# 09-USBUart_PPSMUX_UARTMUX.net
KiCad netlist of a schematic drawn in Altium Designer
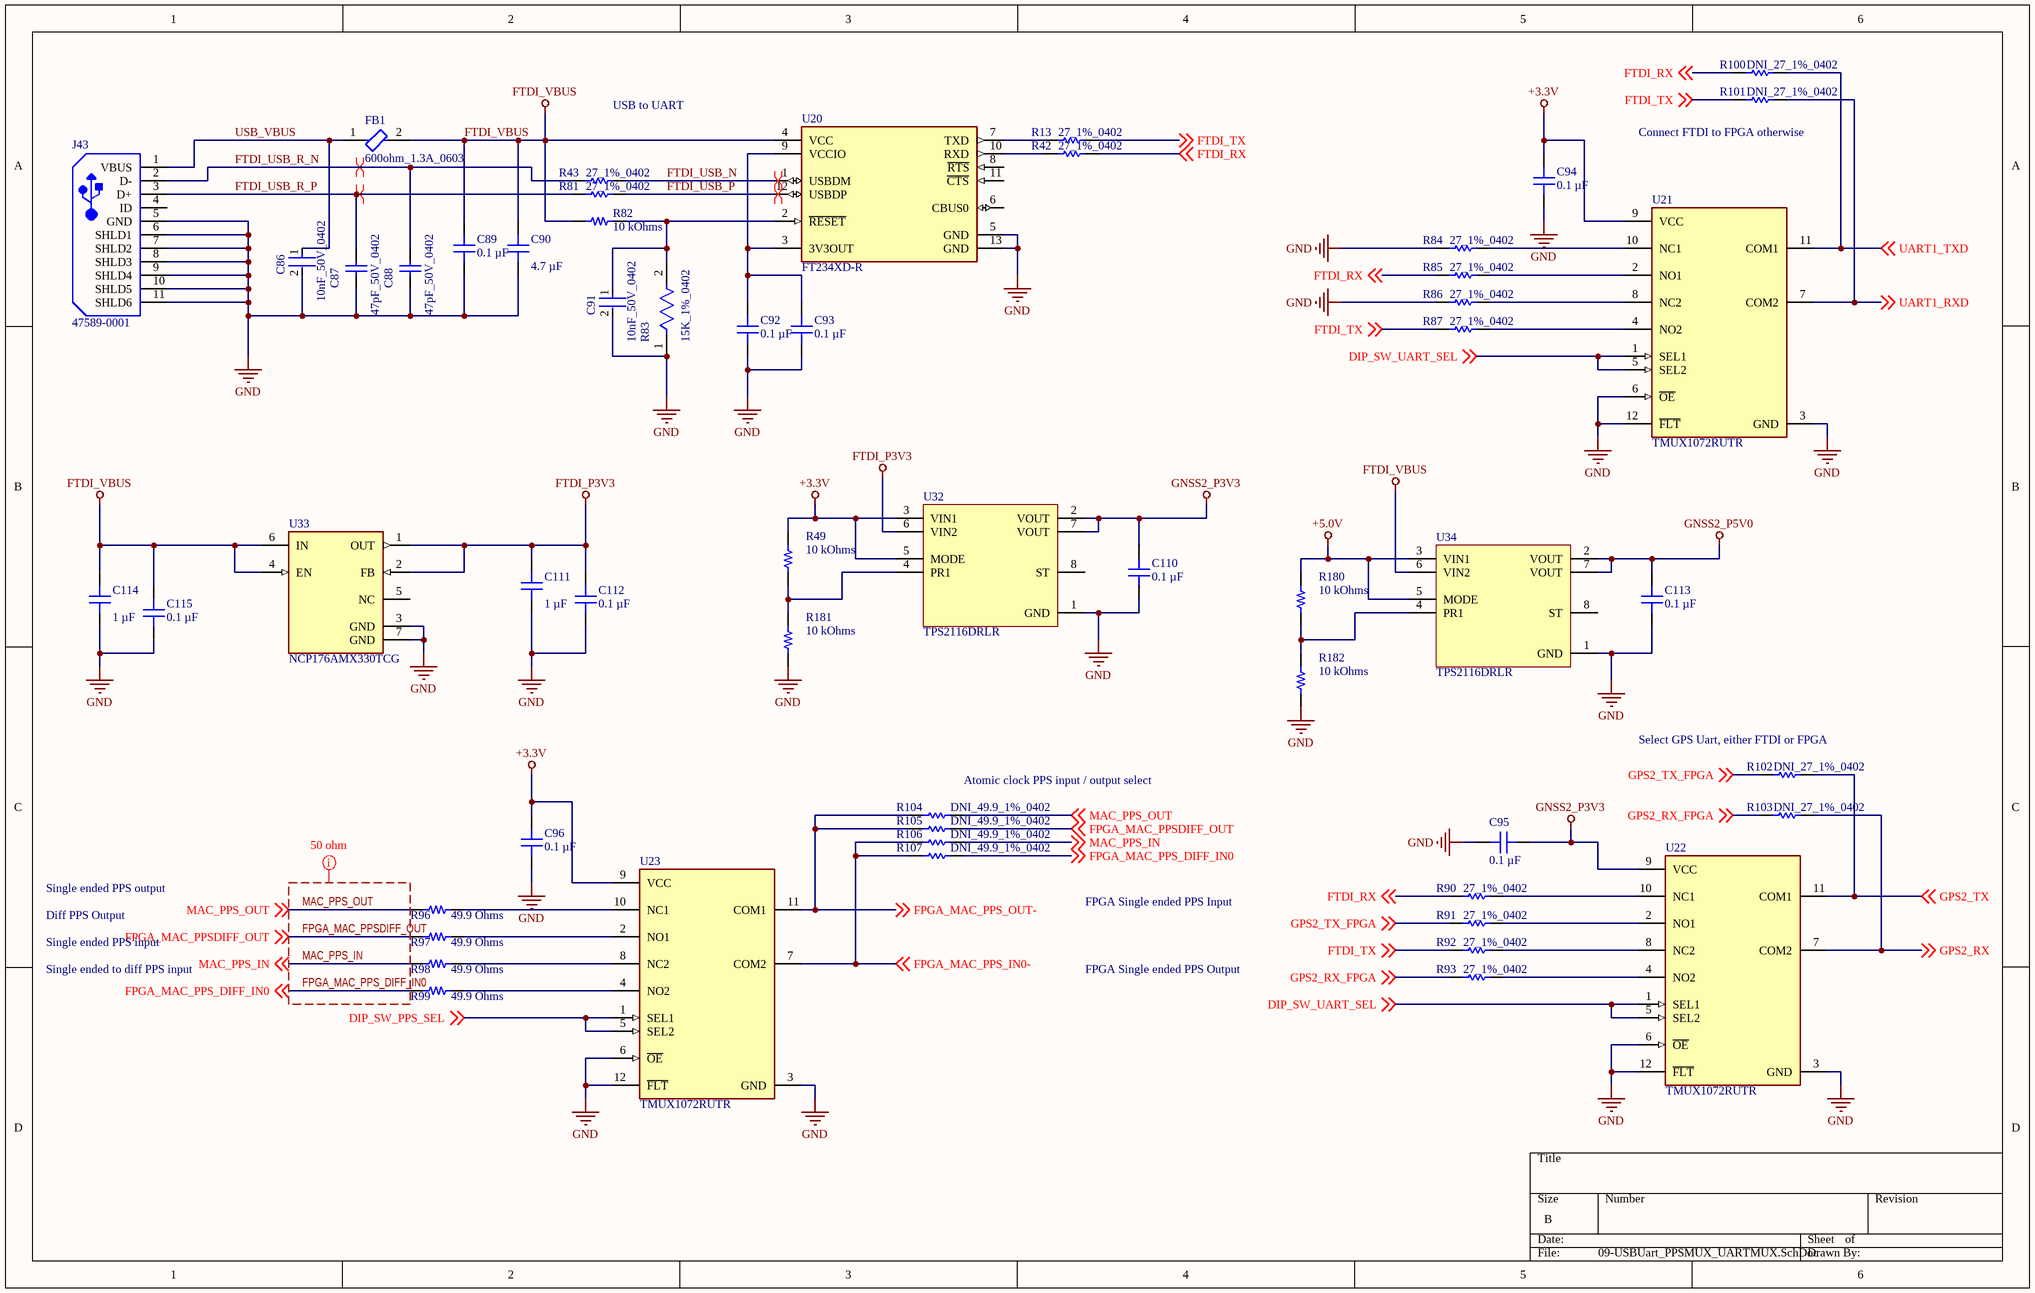
[diagram p0: 09-USBUart_PPSMUX_UARTMUX.SchDoc]

(export (version "E")
  (design (tool "Eeschema 10.0.6"))
  (components
    (comp (ref "C86")
      (value "10nF_50V_0402")
      (footprint "FP-CC0402-MFG")
      (description "CAP CER 10000PF 50V X7R 0402")
      (fields
        (field (name "OCTOPART") "https://octopart.com/cc0402krx7r9bb103-yageo-8376513")
        (field (name "MANUFACTURER PART NUMBER") "CC0402KRX7R9BB103")
      )
      (libsource (lib "Altium Content Vault") (part "11868f565c42a9108669ba33697ecf6"))
    )
    (comp (ref "C87")
      (value "47pF_50V_0402")
      (footprint "CAPC1005X55X25LL05T10")
      (fields (field (name "PART NUMBER") "GRM1555C1H470JA01D") (field (name "MANUFACTURER") "Murata"))
      (libsource (lib "Altium Content Vault") (part "CAP"))
    )
    (comp (ref "C88")
      (value "47pF_50V_0402")
      (footprint "CAPC1005X55X25LL05T10")
      (fields (field (name "PART NUMBER") "GRM1555C1H470JA01D") (field (name "MANUFACTURER") "Murata"))
      (libsource (lib "Altium Content Vault") (part "CAP"))
    )
    (comp (ref "C89")
      (value "0.1 µF")
      (footprint "CAP 0402_1005")
      (description "CAP CER 0.1UF 50V X7R 0402")
      (fields (field (name "TOLERANCE") "±10%") (field (name "PART NUMBER") "CC0402KRX7R9BB104"))
      (libsource (lib "Celestial Altium Library - altium_library") (part "Capacitor"))
    )
    (comp (ref "C90")
      (value "4.7 µF")
      (footprint "MURATA CAP GRM31C 1206_3216")
      (description "CAP CER 4.7UF 50V X7R 1206")
      (fields (field (name "TOLERANCE") "±10%") (field (name "PART NUMBER") "GRM31CR71H475KA12L"))
      (libsource (lib "Celestial Altium Library - altium_library") (part "Capacitor"))
    )
    (comp (ref "C91")
      (value "10nF_50V_0402")
      (footprint "FP-CC0402-MFG")
      (description "CAP CER 10000PF 50V X7R 0402")
      (fields
        (field (name "OCTOPART") "https://octopart.com/cc0402krx7r9bb103-yageo-8376513")
        (field (name "MANUFACTURER PART NUMBER") "CC0402KRX7R9BB103")
      )
      (libsource (lib "Altium Content Vault") (part "11868f565c42a9108669ba33697ecf6"))
    )
    (comp (ref "C92")
      (value "0.1 µF")
      (footprint "CAP 0402_1005")
      (description "CAP CER 0.1UF 50V X7R 0402")
      (fields (field (name "TOLERANCE") "±10%") (field (name "PART NUMBER") "CC0402KRX7R9BB104"))
      (libsource (lib "Celestial Altium Library - altium_library") (part "Capacitor"))
    )
    (comp (ref "C93")
      (value "0.1 µF")
      (footprint "CAP 0402_1005")
      (description "CAP CER 0.1UF 50V X7R 0402")
      (fields (field (name "TOLERANCE") "±10%") (field (name "PART NUMBER") "CC0402KRX7R9BB104"))
      (libsource (lib "Celestial Altium Library - altium_library") (part "Capacitor"))
    )
    (comp (ref "C94")
      (value "0.1 µF")
      (footprint "CAP 0402_1005")
      (description "CAP CER 0.1UF 50V X7R 0402")
      (fields (field (name "TOLERANCE") "±10%") (field (name "PART NUMBER") "CC0402KRX7R9BB104"))
      (libsource (lib "Celestial Altium Library - altium_library") (part "Capacitor"))
    )
    (comp (ref "C95")
      (value "0.1 µF")
      (footprint "CAP 0402_1005")
      (description "CAP CER 0.1UF 50V X7R 0402")
      (fields (field (name "TOLERANCE") "±10%") (field (name "PART NUMBER") "CC0402KRX7R9BB104"))
      (libsource (lib "Celestial Altium Library - altium_library") (part "Capacitor"))
    )
    (comp (ref "C96")
      (value "0.1 µF")
      (footprint "CAP 0402_1005")
      (description "CAP CER 0.1UF 50V X7R 0402")
      (fields (field (name "TOLERANCE") "±10%") (field (name "PART NUMBER") "CC0402KRX7R9BB104"))
      (libsource (lib "Celestial Altium Library - altium_library") (part "Capacitor"))
    )
    (comp (ref "C110")
      (value "0.1 µF")
      (footprint "CAP 0402_1005")
      (description "CAP CER 0.1UF 50V X7R 0402")
      (fields (field (name "TOLERANCE") "±10%") (field (name "PART NUMBER") "CC0402KRX7R9BB104"))
      (libsource (lib "Celestial Altium Library - altium_library") (part "Capacitor"))
    )
    (comp (ref "C111")
      (value "1 µF")
      (footprint "CAP 0402_1005")
      (description "CAP CER 1UF 25V X5R 0402")
      (fields (field (name "TOLERANCE") "±10%") (field (name "PART NUMBER") "CC0402KRX5R8BB105"))
      (libsource (lib "Celestial Altium Library - altium_library") (part "Capacitor"))
    )
    (comp (ref "C112")
      (value "0.1 µF")
      (footprint "CAP 0402_1005")
      (description "CAP CER 0.1UF 50V X7R 0402")
      (fields (field (name "TOLERANCE") "±10%") (field (name "PART NUMBER") "CC0402KRX7R9BB104"))
      (libsource (lib "Celestial Altium Library - altium_library") (part "Capacitor"))
    )
    (comp (ref "C113")
      (value "0.1 µF")
      (footprint "CAP 0402_1005")
      (description "CAP CER 0.1UF 50V X7R 0402")
      (fields (field (name "TOLERANCE") "±10%") (field (name "PART NUMBER") "CC0402KRX7R9BB104"))
      (libsource (lib "Celestial Altium Library - altium_library") (part "Capacitor"))
    )
    (comp (ref "C114")
      (value "1 µF")
      (footprint "CAP 0402_1005")
      (description "CAP CER 1UF 25V X5R 0402")
      (fields (field (name "TOLERANCE") "±10%") (field (name "PART NUMBER") "CC0402KRX5R8BB105"))
      (libsource (lib "Celestial Altium Library - altium_library") (part "Capacitor"))
    )
    (comp (ref "C115")
      (value "0.1 µF")
      (footprint "CAP 0402_1005")
      (description "CAP CER 0.1UF 50V X7R 0402")
      (fields (field (name "TOLERANCE") "±10%") (field (name "PART NUMBER") "CC0402KRX7R9BB104"))
      (libsource (lib "Celestial Altium Library - altium_library") (part "Capacitor"))
    )
    (comp (ref "FB1")
      (value "600ohm_1.3A_0603")
      (footprint "FP-BLM18-0_15-t0_8-IPC_A")
      (description "Chip Ferrite Bead, 0603, 600Ω @ 100MHz, 0.15Ω, 25%, 1.3A")
      (fields (field (name "TOLERANCE") "25%"))
      (libsource (lib "Altium Content Vault") (part "5f30dd21d616792df468990f7003faa"))
    )
    (comp (ref "J43")
      (value "47589-0001")
      (footprint "MOLX-47589-0001_V")
      (description "Right Angle Female Type AB Micro USB Connector, 30 V, 1.8 A, -30 to 85 degC, RoHS, Tape and Reel")
      (fields (field (name "MANUFACTURER") "Molex"))
      (libsource (lib "Altium Content Vault") (part "USB-5-6SHLD"))
    )
    (comp (ref "R13")
      (value "27_1%_0402")
      (footprint "RESC1005X40X25NL05T05")
      (fields (field (name "PART NUMBER") "CRCW040227R0FKED") (field (name "MANUFACTURER") "Vishay Dale"))
      (libsource (lib "Altium Content Vault") (part "RES"))
    )
    (comp (ref "R42")
      (value "27_1%_0402")
      (footprint "RESC1005X40X25NL05T05")
      (fields (field (name "PART NUMBER") "CRCW040227R0FKED") (field (name "MANUFACTURER") "Vishay Dale"))
      (libsource (lib "Altium Content Vault") (part "RES"))
    )
    (comp (ref "R43")
      (value "27_1%_0402")
      (footprint "RESC1005X40X25NL05T05")
      (fields (field (name "PART NUMBER") "CRCW040227R0FKED") (field (name "MANUFACTURER") "Vishay Dale"))
      (libsource (lib "Altium Content Vault") (part "RES"))
    )
    (comp (ref "R49")
      (value "10 kOhms")
      (footprint "YAGEO RES 0402_1005")
      (description "RES 10K OHM 1% 1/16W 0402")
      (fields (field (name "PART NUMBER") "RC0402FR-0710KL") (field (name "MANUFACTURER") "Yageo"))
      (libsource (lib "Celestial Altium Library - altium_library") (part "Resistor"))
    )
    (comp (ref "R81")
      (value "27_1%_0402")
      (footprint "RESC1005X40X25NL05T05")
      (fields (field (name "PART NUMBER") "CRCW040227R0FKED") (field (name "MANUFACTURER") "Vishay Dale"))
      (libsource (lib "Altium Content Vault") (part "RES"))
    )
    (comp (ref "R82")
      (value "10 kOhms")
      (footprint "YAGEO RES 0402_1005")
      (description "RES 10K OHM 1% 1/16W 0402")
      (fields (field (name "PART NUMBER") "RC0402FR-0710KL") (field (name "MANUFACTURER") "Yageo"))
      (libsource (lib "Celestial Altium Library - altium_library") (part "Resistor"))
    )
    (comp (ref "R83")
      (value "15K_1%_0402")
      (footprint "FP-ERJ2R-MFG")
      (description "RES SMD 15K OHM 1% 1/10W 0402")
      (fields (field (name "TOLERANCE") "1%") (field (name "MANUFACTURER PART NUMBER") "ERJ-2RKF1502X"))
      (libsource (lib "Altium Content Vault") (part "1029c3af85768c4190bb7ad29bc67b5"))
    )
    (comp (ref "R84")
      (value "27_1%_0402")
      (footprint "RESC1005X40X25NL05T05")
      (fields (field (name "PART NUMBER") "CRCW040227R0FKED") (field (name "MANUFACTURER") "Vishay Dale"))
      (libsource (lib "Altium Content Vault") (part "RES"))
    )
    (comp (ref "R85")
      (value "27_1%_0402")
      (footprint "RESC1005X40X25NL05T05")
      (fields (field (name "PART NUMBER") "CRCW040227R0FKED") (field (name "MANUFACTURER") "Vishay Dale"))
      (libsource (lib "Altium Content Vault") (part "RES"))
    )
    (comp (ref "R86")
      (value "27_1%_0402")
      (footprint "RESC1005X40X25NL05T05")
      (fields (field (name "PART NUMBER") "CRCW040227R0FKED") (field (name "MANUFACTURER") "Vishay Dale"))
      (libsource (lib "Altium Content Vault") (part "RES"))
    )
    (comp (ref "R87")
      (value "27_1%_0402")
      (footprint "RESC1005X40X25NL05T05")
      (fields (field (name "PART NUMBER") "CRCW040227R0FKED") (field (name "MANUFACTURER") "Vishay Dale"))
      (libsource (lib "Altium Content Vault") (part "RES"))
    )
    (comp (ref "R90")
      (value "27_1%_0402")
      (footprint "RESC1005X40X25NL05T05")
      (fields (field (name "PART NUMBER") "CRCW040227R0FKED") (field (name "MANUFACTURER") "Vishay Dale"))
      (libsource (lib "Altium Content Vault") (part "RES"))
    )
    (comp (ref "R91")
      (value "27_1%_0402")
      (footprint "RESC1005X40X25NL05T05")
      (fields (field (name "PART NUMBER") "CRCW040227R0FKED") (field (name "MANUFACTURER") "Vishay Dale"))
      (libsource (lib "Altium Content Vault") (part "RES"))
    )
    (comp (ref "R92")
      (value "27_1%_0402")
      (footprint "RESC1005X40X25NL05T05")
      (fields (field (name "PART NUMBER") "CRCW040227R0FKED") (field (name "MANUFACTURER") "Vishay Dale"))
      (libsource (lib "Altium Content Vault") (part "RES"))
    )
    (comp (ref "R93")
      (value "27_1%_0402")
      (footprint "RESC1005X40X25NL05T05")
      (fields (field (name "PART NUMBER") "CRCW040227R0FKED") (field (name "MANUFACTURER") "Vishay Dale"))
      (libsource (lib "Altium Content Vault") (part "RES"))
    )
    (comp (ref "R96")
      (value "49.9 Ohms")
      (footprint "YAGEO RES 0402_1005")
      (description "RES 49.9 OHM 1% 1/16W 0402")
      (fields (field (name "MANUFACTURER") "Yageo") (field (name "PART NUMBER") "RC0402FR-0749R9L"))
      (libsource (lib "Celestial Altium Library - altium_library") (part "Resistor"))
    )
    (comp (ref "R97")
      (value "49.9 Ohms")
      (footprint "YAGEO RES 0402_1005")
      (description "RES 49.9 OHM 1% 1/16W 0402")
      (fields (field (name "MANUFACTURER") "Yageo") (field (name "PART NUMBER") "RC0402FR-0749R9L"))
      (libsource (lib "Celestial Altium Library - altium_library") (part "Resistor"))
    )
    (comp (ref "R98")
      (value "49.9 Ohms")
      (footprint "YAGEO RES 0402_1005")
      (description "RES 49.9 OHM 1% 1/16W 0402")
      (fields (field (name "MANUFACTURER") "Yageo") (field (name "PART NUMBER") "RC0402FR-0749R9L"))
      (libsource (lib "Celestial Altium Library - altium_library") (part "Resistor"))
    )
    (comp (ref "R99")
      (value "49.9 Ohms")
      (footprint "YAGEO RES 0402_1005")
      (description "RES 49.9 OHM 1% 1/16W 0402")
      (fields (field (name "MANUFACTURER") "Yageo") (field (name "PART NUMBER") "RC0402FR-0749R9L"))
      (libsource (lib "Celestial Altium Library - altium_library") (part "Resistor"))
    )
    (comp (ref "R100")
      (value "DNI_27_1%_0402")
      (footprint "RESC1005X40X25NL05T05")
      (fields (field (name "PART NUMBER") "CRCW040227R0FKED") (field (name "MANUFACTURER") "Vishay Dale"))
      (libsource (lib "Altium Content Vault") (part "RES"))
    )
    (comp (ref "R101")
      (value "DNI_27_1%_0402")
      (footprint "RESC1005X40X25NL05T05")
      (fields (field (name "PART NUMBER") "CRCW040227R0FKED") (field (name "MANUFACTURER") "Vishay Dale"))
      (libsource (lib "Altium Content Vault") (part "RES"))
    )
    (comp (ref "R102")
      (value "DNI_27_1%_0402")
      (footprint "RESC1005X40X25NL05T05")
      (fields (field (name "PART NUMBER") "CRCW040227R0FKED") (field (name "MANUFACTURER") "Vishay Dale"))
      (libsource (lib "Altium Content Vault") (part "RES"))
    )
    (comp (ref "R103")
      (value "DNI_27_1%_0402")
      (footprint "RESC1005X40X25NL05T05")
      (fields (field (name "PART NUMBER") "CRCW040227R0FKED") (field (name "MANUFACTURER") "Vishay Dale"))
      (libsource (lib "Altium Content Vault") (part "RES"))
    )
    (comp (ref "R104")
      (value "DNI_49.9_1%_0402")
      (footprint "RESC1005X40X25LL05T10")
      (fields (field (name "MANUFACTURER") "Yageo / Phycomp") (field (name "PART NUMBER") "RC0402FR-0749R9L"))
      (libsource (lib "Altium Content Vault") (part "RES"))
    )
    (comp (ref "R105")
      (value "DNI_49.9_1%_0402")
      (footprint "RESC1005X40X25LL05T10")
      (fields (field (name "MANUFACTURER") "Yageo / Phycomp") (field (name "PART NUMBER") "RC0402FR-0749R9L"))
      (libsource (lib "Altium Content Vault") (part "RES"))
    )
    (comp (ref "R106")
      (value "DNI_49.9_1%_0402")
      (footprint "RESC1005X40X25LL05T10")
      (fields (field (name "MANUFACTURER") "Yageo / Phycomp") (field (name "PART NUMBER") "RC0402FR-0749R9L"))
      (libsource (lib "Altium Content Vault") (part "RES"))
    )
    (comp (ref "R107")
      (value "DNI_49.9_1%_0402")
      (footprint "RESC1005X40X25LL05T10")
      (fields (field (name "MANUFACTURER") "Yageo / Phycomp") (field (name "PART NUMBER") "RC0402FR-0749R9L"))
      (libsource (lib "Altium Content Vault") (part "RES"))
    )
    (comp (ref "R180")
      (value "10 kOhms")
      (footprint "YAGEO RES 0402_1005")
      (description "RES 10K OHM 1% 1/16W 0402")
      (fields (field (name "PART NUMBER") "RC0402FR-0710KL") (field (name "MANUFACTURER") "Yageo"))
      (libsource (lib "Celestial Altium Library - altium_library") (part "Resistor"))
    )
    (comp (ref "R181")
      (value "10 kOhms")
      (footprint "YAGEO RES 0402_1005")
      (description "RES 10K OHM 1% 1/16W 0402")
      (fields (field (name "PART NUMBER") "RC0402FR-0710KL") (field (name "MANUFACTURER") "Yageo"))
      (libsource (lib "Celestial Altium Library - altium_library") (part "Resistor"))
    )
    (comp (ref "R182")
      (value "10 kOhms")
      (footprint "YAGEO RES 0402_1005")
      (description "RES 10K OHM 1% 1/16W 0402")
      (fields (field (name "PART NUMBER") "RC0402FR-0710KL") (field (name "MANUFACTURER") "Yageo"))
      (libsource (lib "Celestial Altium Library - altium_library") (part "Resistor"))
    )
    (comp (ref "U20")
      (value "FT234XD-R")
      (footprint "FP-DFN-12-IPC_B")
      (description "IC USB SERIAL BASIC UART 12DFN")
      (libsource (lib "Altium Content Vault") (part "4bef3367ed9f9051bcb84ab46edda1c"))
    )
    (comp (ref "U21")
      (value "TMUX1072RUTR")
      (footprint "FP-RUT0012A-MFG")
      (description "IC SWITCH SPDT DUAL 12UQFN")
      (libsource (lib "Altium Content Vault") (part "12a319ab100cd6cfe745e35972674f5"))
    )
    (comp (ref "U22")
      (value "TMUX1072RUTR")
      (footprint "FP-RUT0012A-MFG")
      (description "IC SWITCH SPDT DUAL 12UQFN")
      (libsource (lib "Altium Content Vault") (part "12a319ab100cd6cfe745e35972674f5"))
    )
    (comp (ref "U23")
      (value "TMUX1072RUTR")
      (footprint "FP-RUT0012A-MFG")
      (description "IC SWITCH SPDT DUAL 12UQFN")
      (libsource (lib "Altium Content Vault") (part "12a319ab100cd6cfe745e35972674f5"))
    )
    (comp (ref "U32")
      (value "TPS2116DRLR")
      (footprint "IC_TPS2116")
      (description "1.6-V to 5.5-V, 40-mΩ, 2.5-A, low-IQ, priority power multiplexer 8-SOT-5X3 -40 to 125")
      (fields (field (name "MF") "Texas Instruments"))
      (libsource (lib "LotusSound") (part "IC_TPS2116DRLR"))
    )
    (comp (ref "U33")
      (value "NCP176AMX330TCG")
      (footprint "FP-711AT-MFG")
      (description "IC REG LINEAR 3.3V 500MA 6XDFN")
      (fields
        (field (name "MANUFACTURER") "ON Semiconductor")
        (field (name "OCTOPART") "https://octopart.com/ncp176amx330tcg-on+semiconductor-61522616")
      )
      (libsource (lib "Altium Content Vault") (part "a38d0f79c2a9f01c07a7e52882ed186"))
    )
    (comp (ref "U34")
      (value "TPS2116DRLR")
      (footprint "IC_TPS2116")
      (description "1.6-V to 5.5-V, 40-mΩ, 2.5-A, low-IQ, priority power multiplexer 8-SOT-5X3 -40 to 125")
      (fields (field (name "MF") "Texas Instruments"))
      (libsource (lib "LotusSound") (part "IC_TPS2116DRLR"))
    )
  )
  (nets
    (net (code "1") (name "+3.3V") (class "Default")
      (node (ref "C94") (pin "1") (pinfunction "1_1") (pintype "passive"))
      (node (ref "C96") (pin "1") (pinfunction "1_1") (pintype "passive"))
      (node (ref "R49") (pin "2") (pinfunction "2_2") (pintype "passive"))
      (node (ref "U21") (pin "9") (pinfunction "VCC_9") (pintype "power_in"))
      (node (ref "U23") (pin "9") (pinfunction "VCC_9") (pintype "power_in"))
      (node (ref "U32") (pin "3") (pinfunction "VIN1_3") (pintype "passive"))
      (node (ref "U32") (pin "5") (pinfunction "MODE_5") (pintype "passive"))
    )
    (net (code "2") (name "+5.0V") (class "Default")
      (node (ref "R180") (pin "2") (pinfunction "2_2") (pintype "passive"))
      (node (ref "U34") (pin "3") (pinfunction "VIN1_3") (pintype "passive"))
      (node (ref "U34") (pin "5") (pinfunction "MODE_5") (pintype "passive"))
    )
    (net (code "3") (name "/FTDI_USB_N") (class "Default")
      (node (ref "R43") (pin "2") (pinfunction "2_2") (pintype "passive"))
      (node (ref "U20") (pin "1") (pinfunction "USBDM_1") (pintype "bidirectional"))
    )
    (net (code "4") (name "/FTDI_USB_P") (class "Default")
      (node (ref "R81") (pin "2") (pinfunction "2_2") (pintype "passive"))
      (node (ref "U20") (pin "12") (pinfunction "USBDP_12") (pintype "bidirectional"))
    )
    (net (code "5") (name "/FTDI_USB_R_N") (class "Default")
      (node (ref "C88") (pin "2") (pinfunction "2_2") (pintype "passive"))
      (node (ref "J43") (pin "2") (pinfunction "D-_2") (pintype "passive"))
      (node (ref "R43") (pin "1") (pinfunction "1_1") (pintype "passive"))
    )
    (net (code "6") (name "/FTDI_USB_R_P") (class "Default")
      (node (ref "C87") (pin "2") (pinfunction "2_2") (pintype "passive"))
      (node (ref "J43") (pin "3") (pinfunction "D+_3") (pintype "passive"))
      (node (ref "R81") (pin "1") (pinfunction "1_1") (pintype "passive"))
    )
    (net (code "7") (name "/USB_VBUS") (class "Default")
      (node (ref "C86") (pin "1") (pinfunction "1_1") (pintype "passive"))
      (node (ref "FB1") (pin "1") (pinfunction "1_1") (pintype "passive"))
      (node (ref "J43") (pin "1") (pinfunction "VBUS_1") (pintype "passive"))
    )
    (net (code "8") (name "DIP_SW_PPS_SEL") (class "Default")
      (node (ref "U23") (pin "1") (pinfunction "SEL1_1") (pintype "input"))
      (node (ref "U23") (pin "5") (pinfunction "SEL2_5") (pintype "input"))
    )
    (net (code "9") (name "DIP_SW_UART_SEL") (class "Default")
      (node (ref "U21") (pin "1") (pinfunction "SEL1_1") (pintype "input"))
      (node (ref "U21") (pin "5") (pinfunction "SEL2_5") (pintype "input"))
      (node (ref "U22") (pin "1") (pinfunction "SEL1_1") (pintype "input"))
      (node (ref "U22") (pin "5") (pinfunction "SEL2_5") (pintype "input"))
    )
    (net (code "10") (name "FPGA_MAC_PPSDIFF_OUT") (class "Default")
      (node (ref "R105") (pin "2") (pinfunction "2_2") (pintype "passive"))
      (node (ref "R97") (pin "1") (pinfunction "1_1") (pintype "passive"))
    )
    (net (code "11") (name "FPGA_MAC_PPS_DIFF_IN0") (class "Default")
      (node (ref "R107") (pin "2") (pinfunction "2_2") (pintype "passive"))
      (node (ref "R99") (pin "1") (pinfunction "1_1") (pintype "passive"))
    )
    (net (code "12") (name "FPGA_MAC_PPS_IN0-") (class "Default")
      (node (ref "R106") (pin "1") (pinfunction "1_1") (pintype "passive"))
      (node (ref "R107") (pin "1") (pinfunction "1_1") (pintype "passive"))
      (node (ref "U23") (pin "7") (pinfunction "COM2_7") (pintype "passive"))
    )
    (net (code "13") (name "FPGA_MAC_PPS_OUT-") (class "Default")
      (node (ref "R104") (pin "1") (pinfunction "1_1") (pintype "passive"))
      (node (ref "R105") (pin "1") (pinfunction "1_1") (pintype "passive"))
      (node (ref "U23") (pin "11") (pinfunction "COM1_11") (pintype "passive"))
    )
    (net (code "14") (name "FTDI_P3V3") (class "Default")
      (node (ref "C111") (pin "2") (pinfunction "2_2") (pintype "passive"))
      (node (ref "C112") (pin "1") (pinfunction "1_1") (pintype "passive"))
      (node (ref "U32") (pin "6") (pinfunction "VIN2_6") (pintype "passive"))
      (node (ref "U33") (pin "1") (pinfunction "OUT_1") (pintype "output"))
      (node (ref "U33") (pin "2") (pinfunction "FB_2") (pintype "input"))
    )
    (net (code "15") (name "FTDI_RX") (class "Default")
      (node (ref "R100") (pin "1") (pinfunction "1_1") (pintype "passive"))
      (node (ref "R42") (pin "2") (pinfunction "2_2") (pintype "passive"))
      (node (ref "R85") (pin "1") (pinfunction "1_1") (pintype "passive"))
      (node (ref "R90") (pin "1") (pinfunction "1_1") (pintype "passive"))
    )
    (net (code "16") (name "FTDI_TX") (class "Default")
      (node (ref "R101") (pin "1") (pinfunction "1_1") (pintype "passive"))
      (node (ref "R13") (pin "2") (pinfunction "2_2") (pintype "passive"))
      (node (ref "R87") (pin "1") (pinfunction "1_1") (pintype "passive"))
      (node (ref "R92") (pin "1") (pinfunction "1_1") (pintype "passive"))
    )
    (net (code "17") (name "FTDI_VBUS") (class "Default")
      (node (ref "C114") (pin "2") (pinfunction "2_2") (pintype "passive"))
      (node (ref "C115") (pin "1") (pinfunction "1_1") (pintype "passive"))
      (node (ref "C89") (pin "1") (pinfunction "1_1") (pintype "passive"))
      (node (ref "C90") (pin "2") (pinfunction "2_2") (pintype "passive"))
      (node (ref "FB1") (pin "2") (pinfunction "2_2") (pintype "passive"))
      (node (ref "R82") (pin "2") (pinfunction "2_2") (pintype "passive"))
      (node (ref "U20") (pin "4") (pinfunction "VCC_4") (pintype "power_in"))
      (node (ref "U33") (pin "4") (pinfunction "EN_4") (pintype "input"))
      (node (ref "U33") (pin "6") (pinfunction "IN_6") (pintype "power_in"))
      (node (ref "U34") (pin "6") (pinfunction "VIN2_6") (pintype "passive"))
    )
    (net (code "18") (name "GND") (class "Default")
      (node (ref "C110") (pin "2") (pinfunction "2_2") (pintype "passive"))
      (node (ref "C111") (pin "1") (pinfunction "1_1") (pintype "passive"))
      (node (ref "C112") (pin "2") (pinfunction "2_2") (pintype "passive"))
      (node (ref "C113") (pin "2") (pinfunction "2_2") (pintype "passive"))
      (node (ref "C114") (pin "1") (pinfunction "1_1") (pintype "passive"))
      (node (ref "C115") (pin "2") (pinfunction "2_2") (pintype "passive"))
      (node (ref "C86") (pin "2") (pinfunction "2_2") (pintype "passive"))
      (node (ref "C87") (pin "1") (pinfunction "1_1") (pintype "passive"))
      (node (ref "C88") (pin "1") (pinfunction "1_1") (pintype "passive"))
      (node (ref "C89") (pin "2") (pinfunction "2_2") (pintype "passive"))
      (node (ref "C90") (pin "1") (pinfunction "1_1") (pintype "passive"))
      (node (ref "C91") (pin "2") (pinfunction "2_2") (pintype "passive"))
      (node (ref "C92") (pin "2") (pinfunction "2_2") (pintype "passive"))
      (node (ref "C93") (pin "2") (pinfunction "2_2") (pintype "passive"))
      (node (ref "C94") (pin "2") (pinfunction "2_2") (pintype "passive"))
      (node (ref "C95") (pin "2") (pinfunction "2_2") (pintype "passive"))
      (node (ref "C96") (pin "2") (pinfunction "2_2") (pintype "passive"))
      (node (ref "J43") (pin "10") (pinfunction "SHLD5_10") (pintype "passive"))
      (node (ref "J43") (pin "11") (pinfunction "SHLD6_11") (pintype "passive"))
      (node (ref "J43") (pin "5") (pinfunction "GND_5") (pintype "passive"))
      (node (ref "J43") (pin "6") (pinfunction "SHLD1_6") (pintype "passive"))
      (node (ref "J43") (pin "7") (pinfunction "SHLD2_7") (pintype "passive"))
      (node (ref "J43") (pin "8") (pinfunction "SHLD3_8") (pintype "passive"))
      (node (ref "J43") (pin "9") (pinfunction "SHLD4_9") (pintype "passive"))
      (node (ref "R181") (pin "1") (pinfunction "1_1") (pintype "passive"))
      (node (ref "R182") (pin "1") (pinfunction "1_1") (pintype "passive"))
      (node (ref "R83") (pin "1") (pinfunction "1_1") (pintype "passive"))
      (node (ref "R84") (pin "1") (pinfunction "1_1") (pintype "passive"))
      (node (ref "R86") (pin "1") (pinfunction "1_1") (pintype "passive"))
      (node (ref "U20") (pin "13") (pinfunction "GND_13") (pintype "power_in"))
      (node (ref "U20") (pin "5") (pinfunction "GND_5") (pintype "power_in"))
      (node (ref "U21") (pin "12") (pinfunction "~{FLT}_12") (pintype "open_collector"))
      (node (ref "U21") (pin "3") (pinfunction "GND_3") (pintype "power_in"))
      (node (ref "U21") (pin "6") (pinfunction "~{OE}_6") (pintype "input"))
      (node (ref "U22") (pin "12") (pinfunction "~{FLT}_12") (pintype "open_collector"))
      (node (ref "U22") (pin "3") (pinfunction "GND_3") (pintype "power_in"))
      (node (ref "U22") (pin "6") (pinfunction "~{OE}_6") (pintype "input"))
      (node (ref "U23") (pin "12") (pinfunction "~{FLT}_12") (pintype "open_collector"))
      (node (ref "U23") (pin "3") (pinfunction "GND_3") (pintype "power_in"))
      (node (ref "U23") (pin "6") (pinfunction "~{OE}_6") (pintype "input"))
      (node (ref "U32") (pin "1") (pinfunction "GND_1") (pintype "passive"))
      (node (ref "U33") (pin "3") (pinfunction "GND_3") (pintype "power_in"))
      (node (ref "U33") (pin "7") (pinfunction "GND_7") (pintype "power_in"))
      (node (ref "U34") (pin "1") (pinfunction "GND_1") (pintype "passive"))
    )
    (net (code "19") (name "GNSS2_P3V3") (class "Default")
      (node (ref "C110") (pin "1") (pinfunction "1_1") (pintype "passive"))
      (node (ref "C95") (pin "1") (pinfunction "1_1") (pintype "passive"))
      (node (ref "U22") (pin "9") (pinfunction "VCC_9") (pintype "power_in"))
      (node (ref "U32") (pin "2") (pinfunction "VOUT_2") (pintype "passive"))
      (node (ref "U32") (pin "7") (pinfunction "VOUT_7") (pintype "passive"))
    )
    (net (code "20") (name "GNSS2_P5V0") (class "Default")
      (node (ref "C113") (pin "1") (pinfunction "1_1") (pintype "passive"))
      (node (ref "U34") (pin "2") (pinfunction "VOUT_2") (pintype "passive"))
      (node (ref "U34") (pin "7") (pinfunction "VOUT_7") (pintype "passive"))
    )
    (net (code "21") (name "GPS2_RX") (class "Default")
      (node (ref "R103") (pin "2") (pinfunction "2_2") (pintype "passive"))
      (node (ref "U22") (pin "7") (pinfunction "COM2_7") (pintype "passive"))
    )
    (net (code "22") (name "GPS2_RX_FPGA") (class "Default")
      (node (ref "R103") (pin "1") (pinfunction "1_1") (pintype "passive"))
      (node (ref "R93") (pin "1") (pinfunction "1_1") (pintype "passive"))
    )
    (net (code "23") (name "GPS2_TX") (class "Default")
      (node (ref "R102") (pin "2") (pinfunction "2_2") (pintype "passive"))
      (node (ref "U22") (pin "11") (pinfunction "COM1_11") (pintype "passive"))
    )
    (net (code "24") (name "GPS2_TX_FPGA") (class "Default")
      (node (ref "R102") (pin "1") (pinfunction "1_1") (pintype "passive"))
      (node (ref "R91") (pin "1") (pinfunction "1_1") (pintype "passive"))
    )
    (net (code "25") (name "MAC_PPS_IN") (class "Default")
      (node (ref "R106") (pin "2") (pinfunction "2_2") (pintype "passive"))
      (node (ref "R98") (pin "1") (pinfunction "1_1") (pintype "passive"))
    )
    (net (code "26") (name "MAC_PPS_OUT") (class "Default")
      (node (ref "R104") (pin "2") (pinfunction "2_2") (pintype "passive"))
      (node (ref "R96") (pin "1") (pinfunction "1_1") (pintype "passive"))
    )
    (net (code "27") (name "Net-(U20-3V3OUT)") (class "Default")
      (node (ref "C92") (pin "1") (pinfunction "1_1") (pintype "passive"))
      (node (ref "C93") (pin "1") (pinfunction "1_1") (pintype "passive"))
      (node (ref "U20") (pin "3") (pinfunction "3V3OUT_3") (pintype "power_in"))
      (node (ref "U20") (pin "9") (pinfunction "VCCIO_9") (pintype "power_in"))
    )
    (net (code "28") (name "Net-(U20-RXD)") (class "Default")
      (node (ref "R42") (pin "1") (pinfunction "1_1") (pintype "passive"))
      (node (ref "U20") (pin "10") (pinfunction "RXD_10") (pintype "output"))
    )
    (net (code "29") (name "Net-(U20-TXD)") (class "Default")
      (node (ref "R13") (pin "1") (pinfunction "1_1") (pintype "passive"))
      (node (ref "U20") (pin "7") (pinfunction "TXD_7") (pintype "output"))
    )
    (net (code "30") (name "Net-(U20-~{RESET})") (class "Default")
      (node (ref "C91") (pin "1") (pinfunction "1_1") (pintype "passive"))
      (node (ref "R82") (pin "1") (pinfunction "1_1") (pintype "passive"))
      (node (ref "R83") (pin "2") (pinfunction "2_2") (pintype "passive"))
      (node (ref "U20") (pin "2") (pinfunction "~{RESET}_2") (pintype "input"))
    )
    (net (code "31") (name "Net-(U21-NC1)") (class "Default")
      (node (ref "R84") (pin "2") (pinfunction "2_2") (pintype "passive"))
      (node (ref "U21") (pin "10") (pinfunction "NC1_10") (pintype "passive"))
    )
    (net (code "32") (name "Net-(U21-NC2)") (class "Default")
      (node (ref "R86") (pin "2") (pinfunction "2_2") (pintype "passive"))
      (node (ref "U21") (pin "8") (pinfunction "NC2_8") (pintype "passive"))
    )
    (net (code "33") (name "Net-(U21-NO1)") (class "Default")
      (node (ref "R85") (pin "2") (pinfunction "2_2") (pintype "passive"))
      (node (ref "U21") (pin "2") (pinfunction "NO1_2") (pintype "passive"))
    )
    (net (code "34") (name "Net-(U21-NO2)") (class "Default")
      (node (ref "R87") (pin "2") (pinfunction "2_2") (pintype "passive"))
      (node (ref "U21") (pin "4") (pinfunction "NO2_4") (pintype "passive"))
    )
    (net (code "35") (name "Net-(U22-NC1)") (class "Default")
      (node (ref "R90") (pin "2") (pinfunction "2_2") (pintype "passive"))
      (node (ref "U22") (pin "10") (pinfunction "NC1_10") (pintype "passive"))
    )
    (net (code "36") (name "Net-(U22-NC2)") (class "Default")
      (node (ref "R92") (pin "2") (pinfunction "2_2") (pintype "passive"))
      (node (ref "U22") (pin "8") (pinfunction "NC2_8") (pintype "passive"))
    )
    (net (code "37") (name "Net-(U22-NO1)") (class "Default")
      (node (ref "R91") (pin "2") (pinfunction "2_2") (pintype "passive"))
      (node (ref "U22") (pin "2") (pinfunction "NO1_2") (pintype "passive"))
    )
    (net (code "38") (name "Net-(U22-NO2)") (class "Default")
      (node (ref "R93") (pin "2") (pinfunction "2_2") (pintype "passive"))
      (node (ref "U22") (pin "4") (pinfunction "NO2_4") (pintype "passive"))
    )
    (net (code "39") (name "Net-(U23-NC1)") (class "Default")
      (node (ref "R96") (pin "2") (pinfunction "2_2") (pintype "passive"))
      (node (ref "U23") (pin "10") (pinfunction "NC1_10") (pintype "passive"))
    )
    (net (code "40") (name "Net-(U23-NC2)") (class "Default")
      (node (ref "R98") (pin "2") (pinfunction "2_2") (pintype "passive"))
      (node (ref "U23") (pin "8") (pinfunction "NC2_8") (pintype "passive"))
    )
    (net (code "41") (name "Net-(U23-NO1)") (class "Default")
      (node (ref "R97") (pin "2") (pinfunction "2_2") (pintype "passive"))
      (node (ref "U23") (pin "2") (pinfunction "NO1_2") (pintype "passive"))
    )
    (net (code "42") (name "Net-(U23-NO2)") (class "Default")
      (node (ref "R99") (pin "2") (pinfunction "2_2") (pintype "passive"))
      (node (ref "U23") (pin "4") (pinfunction "NO2_4") (pintype "passive"))
    )
    (net (code "43") (name "Net-(U32-PR1)") (class "Default")
      (node (ref "R181") (pin "2") (pinfunction "2_2") (pintype "passive"))
      (node (ref "R49") (pin "1") (pinfunction "1_1") (pintype "passive"))
      (node (ref "U32") (pin "4") (pinfunction "PR1_4") (pintype "passive"))
    )
    (net (code "44") (name "Net-(U34-PR1)") (class "Default")
      (node (ref "R180") (pin "1") (pinfunction "1_1") (pintype "passive"))
      (node (ref "R182") (pin "2") (pinfunction "2_2") (pintype "passive"))
      (node (ref "U34") (pin "4") (pinfunction "PR1_4") (pintype "passive"))
    )
    (net (code "45") (name "UART1_RXD") (class "Default")
      (node (ref "R101") (pin "2") (pinfunction "2_2") (pintype "passive"))
      (node (ref "U21") (pin "7") (pinfunction "COM2_7") (pintype "passive"))
    )
    (net (code "46") (name "UART1_TXD") (class "Default")
      (node (ref "R100") (pin "2") (pinfunction "2_2") (pintype "passive"))
      (node (ref "U21") (pin "11") (pinfunction "COM1_11") (pintype "passive"))
    )
    (net (code "47") (name "unconnected-(J43-ID-Pad4)") (class "Default")
      (node (ref "J43") (pin "4") (pinfunction "ID_4") (pintype "passive"))
    )
    (net (code "48") (name "unconnected-(U20-CBUS0-Pad6)") (class "Default")
      (node (ref "U20") (pin "6") (pinfunction "CBUS0_6") (pintype "bidirectional"))
    )
    (net (code "49") (name "unconnected-(U20-~{CTS}-Pad11)") (class "Default")
      (node (ref "U20") (pin "11") (pinfunction "~{CTS}_11") (pintype "input"))
    )
    (net (code "50") (name "unconnected-(U20-~{RTS}-Pad8)") (class "Default")
      (node (ref "U20") (pin "8") (pinfunction "~{RTS}_8") (pintype "input"))
    )
    (net (code "51") (name "unconnected-(U32-ST-Pad8)") (class "Default")
      (node (ref "U32") (pin "8") (pinfunction "ST_8") (pintype "passive"))
    )
    (net (code "52") (name "unconnected-(U33-NC-Pad5)") (class "Default")
      (node (ref "U33") (pin "5") (pinfunction "NC_5") (pintype "passive"))
    )
    (net (code "53") (name "unconnected-(U34-ST-Pad8)") (class "Default")
      (node (ref "U34") (pin "8") (pinfunction "ST_8") (pintype "passive"))
    )
  )
)
